# SCH_plantcare_moisture_module_2025-02-19.net
KiCad netlist of a schematic drawn in EasyEDA
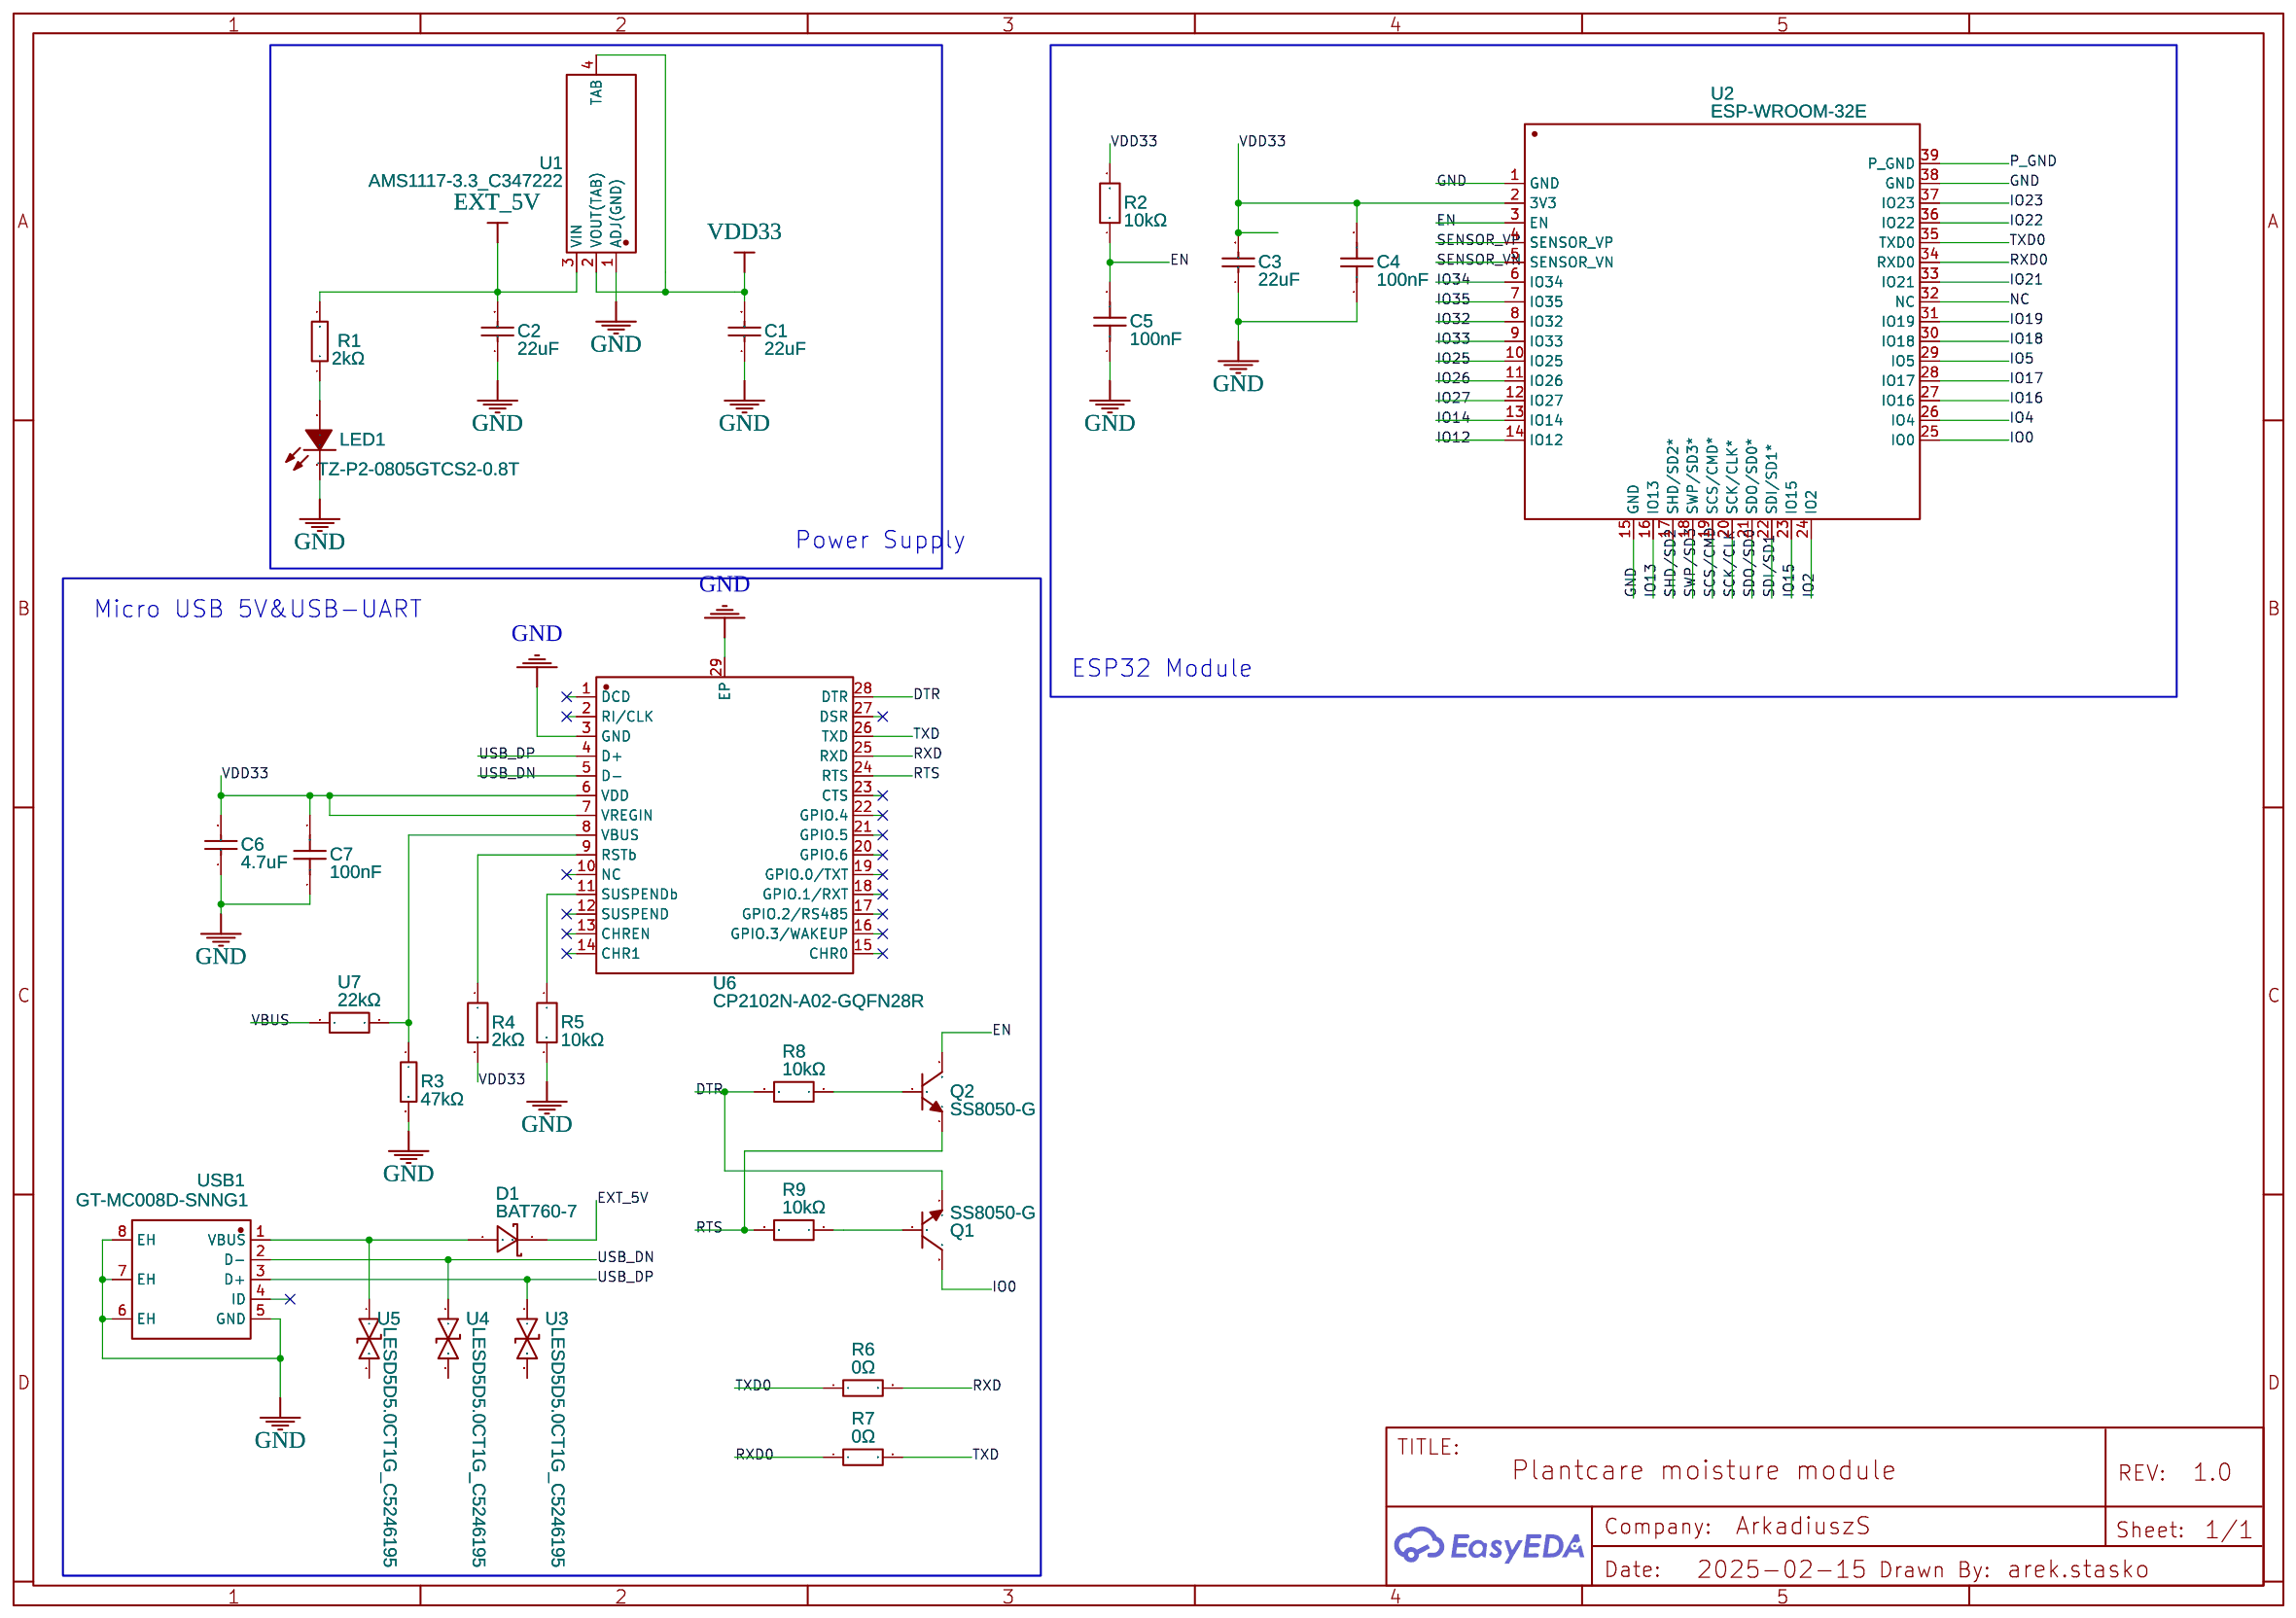
[diagram p0: schematic sheet]

(export (version "E")
  (design (tool "Eeschema 10.0.6"))
  (components
    (comp (ref "C1")
      (value "22uF")
      (fields
        (field (name "Manufacturer Part") "CL21A226MPQNNNE")
        (field (name "Manufacturer") "SAMSUNG(三星)")
      )
      (libsource (lib "") (part "CL21A226MPQNNNE"))
    )
    (comp (ref "C2")
      (value "22uF")
      (fields
        (field (name "Manufacturer Part") "CL21A226MPQNNNE")
        (field (name "Manufacturer") "SAMSUNG(三星)")
      )
      (libsource (lib "") (part "CL21A226MPQNNNE"))
    )
    (comp (ref "C3")
      (value "22uF")
      (fields
        (field (name "Manufacturer Part") "CL21A226MPQNNNE")
        (field (name "Manufacturer") "SAMSUNG(三星)")
      )
      (libsource (lib "") (part "CL21A226MPQNNNE"))
    )
    (comp (ref "C4")
      (value "100nF")
      (fields
        (field (name "Manufacturer Part") "CL10B104KB8NNNC")
        (field (name "Manufacturer") "SAMSUNG(三星)")
      )
      (libsource (lib "") (part "CL10B104KB8NNNC"))
    )
    (comp (ref "C5")
      (value "100nF")
      (fields
        (field (name "Manufacturer Part") "CL10B104KB8NNNC")
        (field (name "Manufacturer") "SAMSUNG(三星)")
      )
      (libsource (lib "") (part "CL10B104KB8NNNC"))
    )
    (comp (ref "C6")
      (value "4.7uF")
      (fields
        (field (name "Manufacturer Part") "CL10A475KP8NNNC")
        (field (name "Manufacturer") "SAMSUNG(三星)")
      )
      (libsource (lib "") (part "CL10A475KP8NNNC"))
    )
    (comp (ref "C7")
      (value "100nF")
      (fields
        (field (name "Manufacturer Part") "CGA0603X7R104K500JT")
        (field (name "Manufacturer") "HRE(芯声)")
      )
      (libsource (lib "") (part "CGA0603X7R104K500JT"))
    )
    (comp (ref "D1")
      (value "BAT760-7")
      (fields (field (name "Manufacturer") "DIODES(美台)"))
      (libsource (lib "") (part "BAT760-7"))
    )
    (comp (ref "LED1")
      (value "TZ-P2-0805GTCS2-0.8T")
      (fields (field (name "Manufacturer") "TUOZHAN(拓展光电)"))
      (libsource (lib "") (part "TZ-P2-0805GTCS2-0.8T"))
    )
    (comp (ref "Q1")
      (value "SS8050-G")
      (fields
        (field (name "Manufacturer Part") "SS8050-G(RANGE:120-200)")
        (field (name "Manufacturer") "CJ(江苏长电/长晶)")
      )
      (libsource (lib "") (part "SS8050-G"))
    )
    (comp (ref "Q2")
      (value "SS8050-G")
      (fields
        (field (name "Manufacturer Part") "SS8050-G(RANGE:120-200)")
        (field (name "Manufacturer") "CJ(江苏长电/长晶)")
      )
      (libsource (lib "") (part "SS8050-G_1"))
    )
    (comp (ref "R1")
      (value "2kΩ")
      (fields
        (field (name "Manufacturer Part") "0603WAF2001T5E")
        (field (name "Manufacturer") "UNI-ROYAL(厚声)")
      )
      (libsource (lib "") (part "0603WAF2001T5E"))
    )
    (comp (ref "R2")
      (value "10kΩ")
      (fields (field (name "Manufacturer Part") "FRC0603J103TS") (field (name "Manufacturer") "FOJAN(富捷)"))
      (libsource (lib "") (part "FRC0603J103TS_1"))
    )
    (comp (ref "R3")
      (value "47kΩ")
      (fields
        (field (name "Manufacturer Part") "0603WAJ0473T5E")
        (field (name "Manufacturer") "UNI-ROYAL(厚声)")
      )
      (libsource (lib "") (part "0603WAJ0473T5E"))
    )
    (comp (ref "R4")
      (value "2kΩ")
      (fields (field (name "Manufacturer Part") "FRC0603J202 TS") (field (name "Manufacturer") "FOJAN(富捷)"))
      (libsource (lib "") (part "FRC0603J202 TS"))
    )
    (comp (ref "R5")
      (value "10kΩ")
      (fields (field (name "Manufacturer Part") "FRC0603J103TS") (field (name "Manufacturer") "FOJAN(富捷)"))
      (libsource (lib "") (part "FRC0603J103TS_2"))
    )
    (comp (ref "R6")
      (value "0Ω")
      (fields
        (field (name "Manufacturer Part") "0603WAJ0000T5E")
        (field (name "Manufacturer") "UNI-ROYAL(厚声)")
      )
      (libsource (lib "") (part "0603WAJ0000T5E"))
    )
    (comp (ref "R7")
      (value "0Ω")
      (fields
        (field (name "Manufacturer Part") "0603WAJ0000T5E")
        (field (name "Manufacturer") "UNI-ROYAL(厚声)")
      )
      (libsource (lib "") (part "0603WAJ0000T5E"))
    )
    (comp (ref "R8")
      (value "10kΩ")
      (fields (field (name "Manufacturer Part") "FRC0603J103TS") (field (name "Manufacturer") "FOJAN(富捷)"))
      (libsource (lib "") (part "FRC0603J103TS"))
    )
    (comp (ref "R9")
      (value "10kΩ")
      (fields (field (name "Manufacturer Part") "FRC0603J103TS") (field (name "Manufacturer") "FOJAN(富捷)"))
      (libsource (lib "") (part "FRC0603J103TS"))
    )
    (comp (ref "U1")
      (value "AMS1117-3.3_C347222")
      (fields (field (name "Manufacturer Part") "AMS1117-3.3") (field (name "Manufacturer") "UMW(友台半导体)"))
      (libsource (lib "") (part "AMS1117-3.3_C347222"))
    )
    (comp (ref "U2")
      (value "ESP-WROOM-32E")
      (fields (field (name "Manufacturer") "DOIT(四博智联)"))
      (libsource (lib "") (part "ESP-WROOM-32E"))
    )
    (comp (ref "U3")
      (value "LESD5D5.0CT1G_C5246195")
      (fields
        (field (name "Manufacturer Part") "LESD5D5.0CT1G")
        (field (name "Manufacturer") "Leiditech(雷卯电子)")
      )
      (libsource (lib "") (part "LESD5D5.0CT1G_C5246195"))
    )
    (comp (ref "U4")
      (value "LESD5D5.0CT1G_C5246195")
      (fields
        (field (name "Manufacturer Part") "LESD5D5.0CT1G")
        (field (name "Manufacturer") "Leiditech(雷卯电子)")
      )
      (libsource (lib "") (part "LESD5D5.0CT1G_C5246195"))
    )
    (comp (ref "U5")
      (value "LESD5D5.0CT1G_C5246195")
      (fields
        (field (name "Manufacturer Part") "LESD5D5.0CT1G")
        (field (name "Manufacturer") "Leiditech(雷卯电子)")
      )
      (libsource (lib "") (part "LESD5D5.0CT1G_C5246195"))
    )
    (comp (ref "U6")
      (value "CP2102N-A02-GQFN28R")
      (fields (field (name "Manufacturer") "SKYWORKS/SILICON LABS(芯科)"))
      (libsource (lib "") (part "CP2102N-A02-GQFN28R"))
    )
    (comp (ref "U7")
      (value "22kΩ")
      (fields (field (name "Manufacturer Part") "FRC0603J223 TS") (field (name "Manufacturer") "FOJAN(富捷)"))
      (libsource (lib "") (part "FRC0603J223 TS"))
    )
    (comp (ref "USB1")
      (value "GT-MC008D-SNNG1")
      (fields (field (name "Manufacturer") "G-Switch(品赞)"))
      (libsource (lib "") (part "GT-MC008D-SNNG1"))
    )
  )
  (nets
    (net (code "1") (name "/DTR") (class "Default")
      (node (ref "Q1") (pin "2") (pinfunction "E_2") (pintype "input"))
      (node (ref "R8") (pin "2") (pinfunction "2_2") (pintype "unspecified"))
      (node (ref "U6") (pin "28") (pinfunction "DTR_28") (pintype "unspecified"))
    )
    (net (code "2") (name "/EN") (class "Default")
      (node (ref "C5") (pin "2") (pinfunction "2_2") (pintype "unspecified"))
      (node (ref "Q2") (pin "3") (pinfunction "C_3") (pintype "input"))
      (node (ref "R2") (pin "1") (pinfunction "1_1") (pintype "unspecified"))
      (node (ref "U2") (pin "3") (pinfunction "EN_3") (pintype "unspecified"))
    )
    (net (code "3") (name "/IO0") (class "Default")
      (node (ref "Q1") (pin "3") (pinfunction "C_3") (pintype "input"))
      (node (ref "U2") (pin "25") (pinfunction "IO0_25") (pintype "unspecified"))
    )
    (net (code "4") (name "/IO2") (class "Default")
      (node (ref "U2") (pin "24") (pinfunction "IO2_24") (pintype "unspecified"))
    )
    (net (code "5") (name "/IO4") (class "Default")
      (node (ref "U2") (pin "26") (pinfunction "IO4_26") (pintype "unspecified"))
    )
    (net (code "6") (name "/IO5") (class "Default")
      (node (ref "U2") (pin "29") (pinfunction "IO5_29") (pintype "unspecified"))
    )
    (net (code "7") (name "/IO12") (class "Default")
      (node (ref "U2") (pin "14") (pinfunction "IO12_14") (pintype "unspecified"))
    )
    (net (code "8") (name "/IO13") (class "Default")
      (node (ref "U2") (pin "16") (pinfunction "IO13_16") (pintype "unspecified"))
    )
    (net (code "9") (name "/IO14") (class "Default")
      (node (ref "U2") (pin "13") (pinfunction "IO14_13") (pintype "unspecified"))
    )
    (net (code "10") (name "/IO15") (class "Default")
      (node (ref "U2") (pin "23") (pinfunction "IO15_23") (pintype "unspecified"))
    )
    (net (code "11") (name "/IO16") (class "Default")
      (node (ref "U2") (pin "27") (pinfunction "IO16_27") (pintype "unspecified"))
    )
    (net (code "12") (name "/IO17") (class "Default")
      (node (ref "U2") (pin "28") (pinfunction "IO17_28") (pintype "unspecified"))
    )
    (net (code "13") (name "/IO18") (class "Default")
      (node (ref "U2") (pin "30") (pinfunction "IO18_30") (pintype "unspecified"))
    )
    (net (code "14") (name "/IO19") (class "Default")
      (node (ref "U2") (pin "31") (pinfunction "IO19_31") (pintype "unspecified"))
    )
    (net (code "15") (name "/IO21") (class "Default")
      (node (ref "U2") (pin "33") (pinfunction "IO21_33") (pintype "unspecified"))
    )
    (net (code "16") (name "/IO22") (class "Default")
      (node (ref "U2") (pin "36") (pinfunction "IO22_36") (pintype "unspecified"))
    )
    (net (code "17") (name "/IO23") (class "Default")
      (node (ref "U2") (pin "37") (pinfunction "IO23_37") (pintype "unspecified"))
    )
    (net (code "18") (name "/IO25") (class "Default")
      (node (ref "U2") (pin "10") (pinfunction "IO25_10") (pintype "unspecified"))
    )
    (net (code "19") (name "/IO26") (class "Default")
      (node (ref "U2") (pin "11") (pinfunction "IO26_11") (pintype "unspecified"))
    )
    (net (code "20") (name "/IO27") (class "Default")
      (node (ref "U2") (pin "12") (pinfunction "IO27_12") (pintype "unspecified"))
    )
    (net (code "21") (name "/IO32") (class "Default")
      (node (ref "U2") (pin "8") (pinfunction "IO32_8") (pintype "unspecified"))
    )
    (net (code "22") (name "/IO33") (class "Default")
      (node (ref "U2") (pin "9") (pinfunction "IO33_9") (pintype "unspecified"))
    )
    (net (code "23") (name "/IO34") (class "Default")
      (node (ref "U2") (pin "6") (pinfunction "IO34_6") (pintype "unspecified"))
    )
    (net (code "24") (name "/IO35") (class "Default")
      (node (ref "U2") (pin "7") (pinfunction "IO35_7") (pintype "unspecified"))
    )
    (net (code "25") (name "/NC") (class "Default")
      (node (ref "U2") (pin "32") (pinfunction "NC_32") (pintype "unspecified"))
    )
    (net (code "26") (name "/P_GND") (class "Default")
      (node (ref "U2") (pin "39") (pinfunction "P_GND_39") (pintype "unspecified"))
    )
    (net (code "27") (name "/RTS") (class "Default")
      (node (ref "Q2") (pin "2") (pinfunction "E_2") (pintype "input"))
      (node (ref "R9") (pin "2") (pinfunction "2_2") (pintype "unspecified"))
      (node (ref "U6") (pin "24") (pinfunction "RTS_24") (pintype "unspecified"))
    )
    (net (code "28") (name "/RXD") (class "Default")
      (node (ref "R6") (pin "2") (pinfunction "2_2") (pintype "input"))
      (node (ref "U6") (pin "25") (pinfunction "RXD_25") (pintype "unspecified"))
    )
    (net (code "29") (name "/RXD0") (class "Default")
      (node (ref "R7") (pin "1") (pinfunction "1_1") (pintype "input"))
      (node (ref "U2") (pin "34") (pinfunction "RXD0_34") (pintype "unspecified"))
    )
    (net (code "30") (name "/SCK{slash}CLK") (class "Default")
      (node (ref "U2") (pin "20") (pinfunction "SCK/CLK*_20") (pintype "unspecified"))
    )
    (net (code "31") (name "/SCS{slash}CMD") (class "Default")
      (node (ref "U2") (pin "19") (pinfunction "SCS/CMD*_19") (pintype "unspecified"))
    )
    (net (code "32") (name "/SDI{slash}SD1") (class "Default")
      (node (ref "U2") (pin "22") (pinfunction "SDI/SD1*_22") (pintype "unspecified"))
    )
    (net (code "33") (name "/SDO{slash}SD0") (class "Default")
      (node (ref "U2") (pin "21") (pinfunction "SDO/SD0*_21") (pintype "unspecified"))
    )
    (net (code "34") (name "/SENSOR_VN") (class "Default")
      (node (ref "U2") (pin "5") (pinfunction "SENSOR_VN_5") (pintype "unspecified"))
    )
    (net (code "35") (name "/SENSOR_VP") (class "Default")
      (node (ref "U2") (pin "4") (pinfunction "SENSOR_VP_4") (pintype "unspecified"))
    )
    (net (code "36") (name "/SHD{slash}SD2") (class "Default")
      (node (ref "U2") (pin "17") (pinfunction "SHD/SD2*_17") (pintype "unspecified"))
    )
    (net (code "37") (name "/SWP{slash}SD3") (class "Default")
      (node (ref "U2") (pin "18") (pinfunction "SWP/SD3*_18") (pintype "unspecified"))
    )
    (net (code "38") (name "/TXD") (class "Default")
      (node (ref "R7") (pin "2") (pinfunction "2_2") (pintype "input"))
      (node (ref "U6") (pin "26") (pinfunction "TXD_26") (pintype "unspecified"))
    )
    (net (code "39") (name "/TXD0") (class "Default")
      (node (ref "R6") (pin "1") (pinfunction "1_1") (pintype "input"))
      (node (ref "U2") (pin "35") (pinfunction "TXD0_35") (pintype "unspecified"))
    )
    (net (code "40") (name "/USB_DN") (class "Default")
      (node (ref "U4") (pin "1") (pinfunction "1_1") (pintype "unspecified"))
      (node (ref "U6") (pin "5") (pinfunction "D-_5") (pintype "unspecified"))
      (node (ref "USB1") (pin "2") (pinfunction "D-_2") (pintype "unspecified"))
    )
    (net (code "41") (name "/USB_DP") (class "Default")
      (node (ref "U3") (pin "1") (pinfunction "1_1") (pintype "unspecified"))
      (node (ref "U6") (pin "4") (pinfunction "D+_4") (pintype "unspecified"))
      (node (ref "USB1") (pin "3") (pinfunction "D+_3") (pintype "unspecified"))
    )
    (net (code "42") (name "/VBUS") (class "Default")
      (node (ref "U7") (pin "1") (pinfunction "1_1") (pintype "unspecified"))
    )
    (net (code "43") (name "EXT_5V") (class "Default")
      (node (ref "C2") (pin "2") (pinfunction "2_2") (pintype "input"))
      (node (ref "D1") (pin "1") (pinfunction "1_1") (pintype "unspecified"))
      (node (ref "R1") (pin "2") (pinfunction "2_2") (pintype "input"))
      (node (ref "U1") (pin "3") (pinfunction "VIN_3") (pintype "unspecified"))
    )
    (net (code "44") (name "GND") (class "Default")
      (node (ref "C1") (pin "1") (pinfunction "1_1") (pintype "input"))
      (node (ref "C2") (pin "1") (pinfunction "1_1") (pintype "input"))
      (node (ref "C3") (pin "1") (pinfunction "1_1") (pintype "input"))
      (node (ref "C4") (pin "1") (pinfunction "1_1") (pintype "unspecified"))
      (node (ref "C5") (pin "1") (pinfunction "1_1") (pintype "unspecified"))
      (node (ref "C6") (pin "1") (pinfunction "1_1") (pintype "input"))
      (node (ref "C7") (pin "1") (pinfunction "1_1") (pintype "unspecified"))
      (node (ref "LED1") (pin "1") (pinfunction "-_1") (pintype "unspecified"))
      (node (ref "R3") (pin "2") (pinfunction "2_2") (pintype "input"))
      (node (ref "R5") (pin "2") (pinfunction "2_2") (pintype "unspecified"))
      (node (ref "U1") (pin "1") (pinfunction "ADJ(GND)_1") (pintype "unspecified"))
      (node (ref "U2") (pin "1") (pinfunction "GND_1") (pintype "unspecified"))
      (node (ref "U2") (pin "15") (pinfunction "GND_15") (pintype "unspecified"))
      (node (ref "U2") (pin "38") (pinfunction "GND_38") (pintype "unspecified"))
      (node (ref "U6") (pin "29") (pinfunction "EP_29") (pintype "unspecified"))
      (node (ref "U6") (pin "3") (pinfunction "GND_3") (pintype "unspecified"))
      (node (ref "USB1") (pin "5") (pinfunction "GND_5") (pintype "unspecified"))
      (node (ref "USB1") (pin "6") (pinfunction "EH_6") (pintype "unspecified"))
      (node (ref "USB1") (pin "7") (pinfunction "EH_7") (pintype "unspecified"))
      (node (ref "USB1") (pin "8") (pinfunction "EH_8") (pintype "unspecified"))
    )
    (net (code "45") (name "Net-(LED1-+)") (class "Default")
      (node (ref "LED1") (pin "2") (pinfunction "+_2") (pintype "unspecified"))
      (node (ref "R1") (pin "1") (pinfunction "1_1") (pintype "input"))
    )
    (net (code "46") (name "Net-(Q1-B)") (class "Default")
      (node (ref "Q1") (pin "1") (pinfunction "B_1") (pintype "input"))
      (node (ref "R9") (pin "1") (pinfunction "1_1") (pintype "unspecified"))
    )
    (net (code "47") (name "Net-(Q2-B)") (class "Default")
      (node (ref "Q2") (pin "1") (pinfunction "B_1") (pintype "input"))
      (node (ref "R8") (pin "1") (pinfunction "1_1") (pintype "unspecified"))
    )
    (net (code "48") (name "Net-(U6-RSTb)") (class "Default")
      (node (ref "R4") (pin "1") (pinfunction "1_1") (pintype "unspecified"))
      (node (ref "U6") (pin "9") (pinfunction "RSTb_9") (pintype "unspecified"))
    )
    (net (code "49") (name "Net-(U6-SUSPENDb)") (class "Default")
      (node (ref "R5") (pin "1") (pinfunction "1_1") (pintype "unspecified"))
      (node (ref "U6") (pin "11") (pinfunction "SUSPENDb_11") (pintype "unspecified"))
    )
    (net (code "50") (name "Net-(U6-VBUS)") (class "Default")
      (node (ref "R3") (pin "1") (pinfunction "1_1") (pintype "input"))
      (node (ref "U6") (pin "8") (pinfunction "VBUS_8") (pintype "unspecified"))
      (node (ref "U7") (pin "2") (pinfunction "2_2") (pintype "unspecified"))
    )
    (net (code "51") (name "Net-(USB1-VBUS)") (class "Default")
      (node (ref "D1") (pin "2") (pinfunction "2_2") (pintype "unspecified"))
      (node (ref "U5") (pin "1") (pinfunction "1_1") (pintype "unspecified"))
      (node (ref "USB1") (pin "1") (pinfunction "VBUS_1") (pintype "unspecified"))
    )
    (net (code "52") (name "VDD33") (class "Default")
      (node (ref "C1") (pin "2") (pinfunction "2_2") (pintype "input"))
      (node (ref "C3") (pin "2") (pinfunction "2_2") (pintype "input"))
      (node (ref "C4") (pin "2") (pinfunction "2_2") (pintype "unspecified"))
      (node (ref "C6") (pin "2") (pinfunction "2_2") (pintype "input"))
      (node (ref "C7") (pin "2") (pinfunction "2_2") (pintype "unspecified"))
      (node (ref "R2") (pin "2") (pinfunction "2_2") (pintype "unspecified"))
      (node (ref "R4") (pin "2") (pinfunction "2_2") (pintype "unspecified"))
      (node (ref "U1") (pin "2") (pinfunction "VOUT(TAB)_2") (pintype "unspecified"))
      (node (ref "U1") (pin "4") (pinfunction "TAB_4") (pintype "unspecified"))
      (node (ref "U2") (pin "2") (pinfunction "3V3_2") (pintype "unspecified"))
      (node (ref "U6") (pin "6") (pinfunction "VDD_6") (pintype "unspecified"))
      (node (ref "U6") (pin "7") (pinfunction "VREGIN_7") (pintype "unspecified"))
    )
    (net (code "53") (name "unconnected-(U3-Pad2)") (class "Default")
      (node (ref "U3") (pin "2") (pinfunction "2_2") (pintype "unspecified"))
    )
    (net (code "54") (name "unconnected-(U4-Pad2)") (class "Default")
      (node (ref "U4") (pin "2") (pinfunction "2_2") (pintype "unspecified"))
    )
    (net (code "55") (name "unconnected-(U5-Pad2)") (class "Default")
      (node (ref "U5") (pin "2") (pinfunction "2_2") (pintype "unspecified"))
    )
    (net (code "56") (name "unconnected-(U6-CHR0-Pad15)") (class "Default")
      (node (ref "U6") (pin "15") (pinfunction "CHR0_15") (pintype "unspecified+no_connect"))
    )
    (net (code "57") (name "unconnected-(U6-CHR1-Pad14)") (class "Default")
      (node (ref "U6") (pin "14") (pinfunction "CHR1_14") (pintype "unspecified+no_connect"))
    )
    (net (code "58") (name "unconnected-(U6-CHREN-Pad13)") (class "Default")
      (node (ref "U6") (pin "13") (pinfunction "CHREN_13") (pintype "unspecified+no_connect"))
    )
    (net (code "59") (name "unconnected-(U6-CTS-Pad23)") (class "Default")
      (node (ref "U6") (pin "23") (pinfunction "CTS_23") (pintype "unspecified+no_connect"))
    )
    (net (code "60") (name "unconnected-(U6-DCD-Pad1)") (class "Default")
      (node (ref "U6") (pin "1") (pinfunction "DCD_1") (pintype "unspecified+no_connect"))
    )
    (net (code "61") (name "unconnected-(U6-DSR-Pad27)") (class "Default")
      (node (ref "U6") (pin "27") (pinfunction "DSR_27") (pintype "unspecified+no_connect"))
    )
    (net (code "62") (name "unconnected-(U6-GPIO.0{slash}TXT-Pad19)") (class "Default")
      (node (ref "U6") (pin "19") (pinfunction "GPIO.0/TXT_19") (pintype "unspecified+no_connect"))
    )
    (net (code "63") (name "unconnected-(U6-GPIO.1{slash}RXT-Pad18)") (class "Default")
      (node (ref "U6") (pin "18") (pinfunction "GPIO.1/RXT_18") (pintype "unspecified+no_connect"))
    )
    (net (code "64") (name "unconnected-(U6-GPIO.2{slash}RS485-Pad17)") (class "Default")
      (node (ref "U6") (pin "17") (pinfunction "GPIO.2/RS485_17") (pintype "unspecified+no_connect"))
    )
    (net (code "65") (name "unconnected-(U6-GPIO.3{slash}WAKEUP-Pad16)") (class "Default")
      (node (ref "U6") (pin "16") (pinfunction "GPIO.3/WAKEUP_16") (pintype "unspecified+no_connect"))
    )
    (net (code "66") (name "unconnected-(U6-GPIO.4-Pad22)") (class "Default")
      (node (ref "U6") (pin "22") (pinfunction "GPIO.4_22") (pintype "unspecified+no_connect"))
    )
    (net (code "67") (name "unconnected-(U6-GPIO.5-Pad21)") (class "Default")
      (node (ref "U6") (pin "21") (pinfunction "GPIO.5_21") (pintype "unspecified+no_connect"))
    )
    (net (code "68") (name "unconnected-(U6-GPIO.6-Pad20)") (class "Default")
      (node (ref "U6") (pin "20") (pinfunction "GPIO.6_20") (pintype "unspecified+no_connect"))
    )
    (net (code "69") (name "unconnected-(U6-NC-Pad10)") (class "Default")
      (node (ref "U6") (pin "10") (pinfunction "NC_10") (pintype "unspecified+no_connect"))
    )
    (net (code "70") (name "unconnected-(U6-RI{slash}CLK-Pad2)") (class "Default")
      (node (ref "U6") (pin "2") (pinfunction "RI/CLK_2") (pintype "unspecified+no_connect"))
    )
    (net (code "71") (name "unconnected-(U6-SUSPEND-Pad12)") (class "Default")
      (node (ref "U6") (pin "12") (pinfunction "SUSPEND_12") (pintype "unspecified+no_connect"))
    )
    (net (code "72") (name "unconnected-(USB1-ID-Pad4)") (class "Default")
      (node (ref "USB1") (pin "4") (pinfunction "ID_4") (pintype "unspecified+no_connect"))
    )
  )
)
